# EST_MainV20_Output.net
KiCad netlist of a schematic drawn in Altium Designer
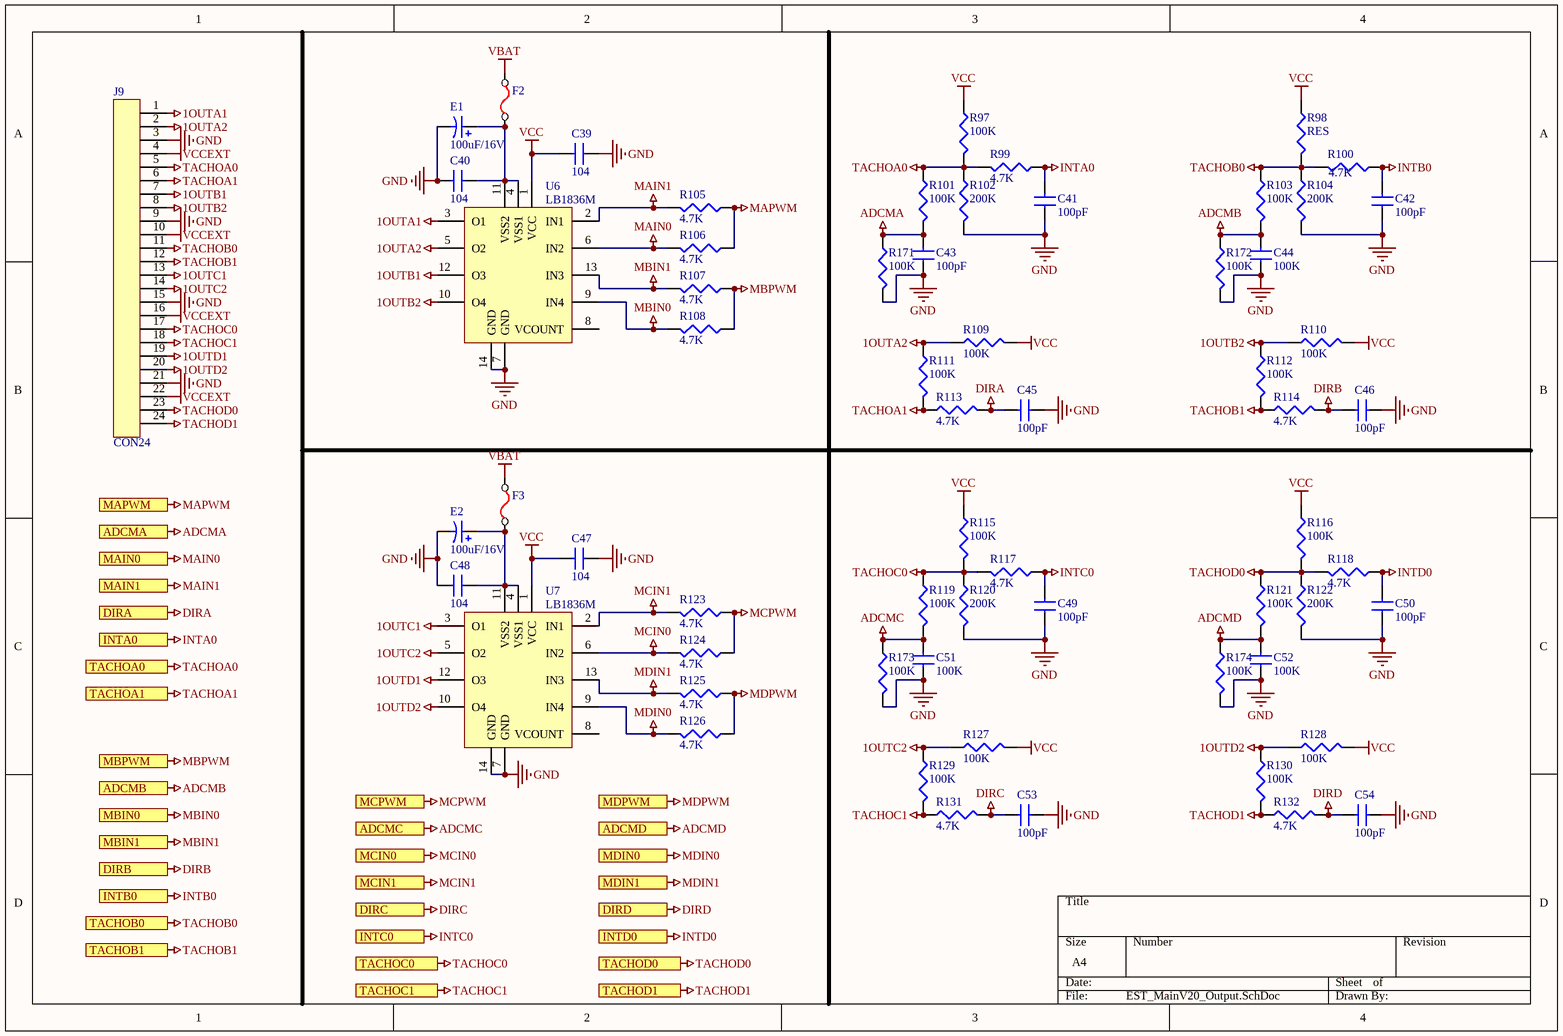
[diagram p0: EST_MainV20_Output.SchDoc]

(export (version "E")
  (design (tool "Eeschema 10.0.6"))
  (components
    (comp (ref "C39")
      (value "104")
      (footprint "CAP_0603")
      (description "Capacitor")
      (libsource (lib "模拟器件") (part "CAP"))
    )
    (comp (ref "C40")
      (value "104")
      (footprint "CAP_0603")
      (description "Capacitor")
      (libsource (lib "模拟器件") (part "CAP"))
    )
    (comp (ref "C41")
      (value "100pF")
      (footprint "CAP_0603")
      (description "Capacitor")
      (libsource (lib "模拟器件") (part "CAP"))
    )
    (comp (ref "C42")
      (value "100pF")
      (footprint "CAP_0603")
      (description "Capacitor")
      (libsource (lib "模拟器件") (part "CAP"))
    )
    (comp (ref "C43")
      (value "100pF")
      (footprint "CAP_0603")
      (description "Capacitor")
      (libsource (lib "模拟器件") (part "CAP"))
    )
    (comp (ref "C44")
      (value "100K")
      (footprint "CAP_0603")
      (description "Capacitor")
      (libsource (lib "模拟器件") (part "CAP"))
    )
    (comp (ref "C45")
      (value "100pF")
      (footprint "CAP_0603")
      (description "Capacitor")
      (libsource (lib "模拟器件") (part "CAP"))
    )
    (comp (ref "C46")
      (value "100pF")
      (footprint "CAP_0603")
      (description "Capacitor")
      (libsource (lib "模拟器件") (part "CAP"))
    )
    (comp (ref "C47")
      (value "104")
      (footprint "CAP_0603")
      (description "Capacitor")
      (libsource (lib "模拟器件") (part "CAP"))
    )
    (comp (ref "C48")
      (value "104")
      (footprint "CAP_0603")
      (description "Capacitor")
      (libsource (lib "模拟器件") (part "CAP"))
    )
    (comp (ref "C49")
      (value "100pF")
      (footprint "CAP_0603")
      (description "Capacitor")
      (libsource (lib "模拟器件") (part "CAP"))
    )
    (comp (ref "C50")
      (value "100pF")
      (footprint "CAP_0603")
      (description "Capacitor")
      (libsource (lib "模拟器件") (part "CAP"))
    )
    (comp (ref "C51")
      (value "100K")
      (footprint "CAP_0603")
      (description "Capacitor")
      (libsource (lib "模拟器件") (part "CAP"))
    )
    (comp (ref "C52")
      (value "100K")
      (footprint "CAP_0603")
      (description "Capacitor")
      (libsource (lib "模拟器件") (part "CAP"))
    )
    (comp (ref "C53")
      (value "100pF")
      (footprint "CAP_0603")
      (description "Capacitor")
      (libsource (lib "模拟器件") (part "CAP"))
    )
    (comp (ref "C54")
      (value "100pF")
      (footprint "CAP_0603")
      (description "Capacitor")
      (libsource (lib "模拟器件") (part "CAP"))
    )
    (comp (ref "E1")
      (value "100uF/16V")
      (footprint "1812")
      (description "Bi-Polar Capacitor")
      (libsource (lib "模拟器件") (part "CAP2"))
    )
    (comp (ref "E2")
      (value "100uF/16V")
      (footprint "1812")
      (description "Bi-Polar Capacitor")
      (libsource (lib "模拟器件") (part "CAP2"))
    )
    (comp (ref "F2")
      (value "FUSE")
      (footprint "1812")
      (description "Fuse")
      (libsource (lib "模拟器件") (part "FUSE"))
    )
    (comp (ref "F3")
      (value "FUSE")
      (footprint "1812")
      (description "Fuse")
      (libsource (lib "模拟器件") (part "FUSE"))
    )
    (comp (ref "J9") (value "CON24") (footprint "RJ11-4") (libsource (lib "模拟器件") (part "CON24")))
    (comp (ref "R97")
      (value "100K")
      (footprint "RES_0603")
      (description "Resistor")
      (libsource (lib "模拟器件") (part "RES"))
    )
    (comp (ref "R98")
      (value "RES")
      (footprint "RES_0603")
      (description "Resistor")
      (libsource (lib "模拟器件") (part "RES"))
    )
    (comp (ref "R99")
      (value "4.7K")
      (footprint "RES_0603")
      (description "Resistor")
      (libsource (lib "模拟器件") (part "RES"))
    )
    (comp (ref "R100")
      (value "4.7K")
      (footprint "RES_0603")
      (description "Resistor")
      (libsource (lib "模拟器件") (part "RES"))
    )
    (comp (ref "R101")
      (value "100K")
      (footprint "RES_0603")
      (description "Resistor")
      (libsource (lib "模拟器件") (part "RES"))
    )
    (comp (ref "R102")
      (value "200K")
      (footprint "RES_0603")
      (description "Resistor")
      (libsource (lib "模拟器件") (part "RES"))
    )
    (comp (ref "R103")
      (value "100K")
      (footprint "RES_0603")
      (description "Resistor")
      (libsource (lib "模拟器件") (part "RES"))
    )
    (comp (ref "R104")
      (value "200K")
      (footprint "RES_0603")
      (description "Resistor")
      (libsource (lib "模拟器件") (part "RES"))
    )
    (comp (ref "R105")
      (value "4.7K")
      (footprint "RES_0603")
      (description "Resistor")
      (libsource (lib "模拟器件") (part "RES"))
    )
    (comp (ref "R106")
      (value "4.7K")
      (footprint "RES_0603")
      (description "Resistor")
      (libsource (lib "模拟器件") (part "RES"))
    )
    (comp (ref "R107")
      (value "4.7K")
      (footprint "RES_0603")
      (description "Resistor")
      (libsource (lib "模拟器件") (part "RES"))
    )
    (comp (ref "R108")
      (value "4.7K")
      (footprint "RES_0603")
      (description "Resistor")
      (libsource (lib "模拟器件") (part "RES"))
    )
    (comp (ref "R109")
      (value "100K")
      (footprint "RES_0603")
      (description "Resistor")
      (libsource (lib "模拟器件") (part "RES"))
    )
    (comp (ref "R110")
      (value "100K")
      (footprint "RES_0603")
      (description "Resistor")
      (libsource (lib "模拟器件") (part "RES"))
    )
    (comp (ref "R111")
      (value "100K")
      (footprint "RES_0603")
      (description "Resistor")
      (libsource (lib "模拟器件") (part "RES"))
    )
    (comp (ref "R112")
      (value "100K")
      (footprint "RES_0603")
      (description "Resistor")
      (libsource (lib "模拟器件") (part "RES"))
    )
    (comp (ref "R113")
      (value "4.7K")
      (footprint "RES_0603")
      (description "Resistor")
      (libsource (lib "模拟器件") (part "RES"))
    )
    (comp (ref "R114")
      (value "4.7K")
      (footprint "RES_0603")
      (description "Resistor")
      (libsource (lib "模拟器件") (part "RES"))
    )
    (comp (ref "R115")
      (value "100K")
      (footprint "RES_0603")
      (description "Resistor")
      (libsource (lib "模拟器件") (part "RES"))
    )
    (comp (ref "R116")
      (value "100K")
      (footprint "RES_0603")
      (description "Resistor")
      (libsource (lib "模拟器件") (part "RES"))
    )
    (comp (ref "R117")
      (value "4.7K")
      (footprint "RES_0603")
      (description "Resistor")
      (libsource (lib "模拟器件") (part "RES"))
    )
    (comp (ref "R118")
      (value "4.7K")
      (footprint "RES_0603")
      (description "Resistor")
      (libsource (lib "模拟器件") (part "RES"))
    )
    (comp (ref "R119")
      (value "100K")
      (footprint "RES_0603")
      (description "Resistor")
      (libsource (lib "模拟器件") (part "RES"))
    )
    (comp (ref "R120")
      (value "200K")
      (footprint "RES_0603")
      (description "Resistor")
      (libsource (lib "模拟器件") (part "RES"))
    )
    (comp (ref "R121")
      (value "100K")
      (footprint "RES_0603")
      (description "Resistor")
      (libsource (lib "模拟器件") (part "RES"))
    )
    (comp (ref "R122")
      (value "200K")
      (footprint "RES_0603")
      (description "Resistor")
      (libsource (lib "模拟器件") (part "RES"))
    )
    (comp (ref "R123")
      (value "4.7K")
      (footprint "RES_0603")
      (description "Resistor")
      (libsource (lib "模拟器件") (part "RES"))
    )
    (comp (ref "R124")
      (value "4.7K")
      (footprint "RES_0603")
      (description "Resistor")
      (libsource (lib "模拟器件") (part "RES"))
    )
    (comp (ref "R125")
      (value "4.7K")
      (footprint "RES_0603")
      (description "Resistor")
      (libsource (lib "模拟器件") (part "RES"))
    )
    (comp (ref "R126")
      (value "4.7K")
      (footprint "RES_0603")
      (description "Resistor")
      (libsource (lib "模拟器件") (part "RES"))
    )
    (comp (ref "R127")
      (value "100K")
      (footprint "RES_0603")
      (description "Resistor")
      (libsource (lib "模拟器件") (part "RES"))
    )
    (comp (ref "R128")
      (value "100K")
      (footprint "RES_0603")
      (description "Resistor")
      (libsource (lib "模拟器件") (part "RES"))
    )
    (comp (ref "R129")
      (value "100K")
      (footprint "RES_0603")
      (description "Resistor")
      (libsource (lib "模拟器件") (part "RES"))
    )
    (comp (ref "R130")
      (value "100K")
      (footprint "RES_0603")
      (description "Resistor")
      (libsource (lib "模拟器件") (part "RES"))
    )
    (comp (ref "R131")
      (value "4.7K")
      (footprint "RES_0603")
      (description "Resistor")
      (libsource (lib "模拟器件") (part "RES"))
    )
    (comp (ref "R132")
      (value "4.7K")
      (footprint "RES_0603")
      (description "Resistor")
      (libsource (lib "模拟器件") (part "RES"))
    )
    (comp (ref "R171")
      (value "100K")
      (footprint "RES_0603")
      (description "Resistor")
      (libsource (lib "模拟器件") (part "RES"))
    )
    (comp (ref "R172")
      (value "100K")
      (footprint "RES_0603")
      (description "Resistor")
      (libsource (lib "模拟器件") (part "RES"))
    )
    (comp (ref "R173")
      (value "100K")
      (footprint "RES_0603")
      (description "Resistor")
      (libsource (lib "模拟器件") (part "RES"))
    )
    (comp (ref "R174")
      (value "100K")
      (footprint "RES_0603")
      (description "Resistor")
      (libsource (lib "模拟器件") (part "RES"))
    )
    (comp (ref "U6") (value "LB1836M") (footprint "LB1836") (libsource (lib "其它") (part "LM1836")))
    (comp (ref "U7") (value "LB1836M") (footprint "LB1836") (libsource (lib "其它") (part "LM1836")))
  )
  (nets
    (net (code "1") (name "1OUTA1") (class "Default")
      (node (ref "J9") (pin "1") (pinfunction "1_1") (pintype "passive"))
      (node (ref "U6") (pin "3") (pinfunction "O1_3") (pintype "passive"))
    )
    (net (code "2") (name "1OUTA2") (class "Default")
      (node (ref "J9") (pin "2") (pinfunction "2_2") (pintype "passive"))
      (node (ref "R109") (pin "2") (pinfunction "BOT_2") (pintype "passive"))
      (node (ref "R111") (pin "2") (pinfunction "BOT_2") (pintype "passive"))
      (node (ref "U6") (pin "5") (pinfunction "O2_5") (pintype "passive"))
    )
    (net (code "3") (name "1OUTB1") (class "Default")
      (node (ref "J9") (pin "7") (pinfunction "7_7") (pintype "passive"))
      (node (ref "U6") (pin "12") (pinfunction "O3_12") (pintype "passive"))
    )
    (net (code "4") (name "1OUTB2") (class "Default")
      (node (ref "J9") (pin "8") (pinfunction "8_8") (pintype "passive"))
      (node (ref "R110") (pin "2") (pinfunction "BOT_2") (pintype "passive"))
      (node (ref "R112") (pin "2") (pinfunction "BOT_2") (pintype "passive"))
      (node (ref "U6") (pin "10") (pinfunction "O4_10") (pintype "passive"))
    )
    (net (code "5") (name "1OUTC1") (class "Default")
      (node (ref "J9") (pin "13") (pinfunction "13_13") (pintype "passive"))
      (node (ref "U7") (pin "3") (pinfunction "O1_3") (pintype "passive"))
    )
    (net (code "6") (name "1OUTC2") (class "Default")
      (node (ref "J9") (pin "14") (pinfunction "14_14") (pintype "passive"))
      (node (ref "R127") (pin "2") (pinfunction "BOT_2") (pintype "passive"))
      (node (ref "R129") (pin "2") (pinfunction "BOT_2") (pintype "passive"))
      (node (ref "U7") (pin "5") (pinfunction "O2_5") (pintype "passive"))
    )
    (net (code "7") (name "1OUTD1") (class "Default")
      (node (ref "J9") (pin "19") (pinfunction "19_19") (pintype "passive"))
      (node (ref "U7") (pin "12") (pinfunction "O3_12") (pintype "passive"))
    )
    (net (code "8") (name "1OUTD2") (class "Default")
      (node (ref "J9") (pin "20") (pinfunction "20_20") (pintype "passive"))
      (node (ref "R128") (pin "2") (pinfunction "BOT_2") (pintype "passive"))
      (node (ref "R130") (pin "2") (pinfunction "BOT_2") (pintype "passive"))
      (node (ref "U7") (pin "10") (pinfunction "O4_10") (pintype "passive"))
    )
    (net (code "9") (name "ADCMA") (class "Default")
      (node (ref "C43") (pin "2") (pinfunction "2_2") (pintype "passive"))
      (node (ref "R101") (pin "1") (pinfunction "TOP_1") (pintype "passive"))
      (node (ref "R171") (pin "2") (pinfunction "BOT_2") (pintype "passive"))
    )
    (net (code "10") (name "ADCMB") (class "Default")
      (node (ref "C44") (pin "2") (pinfunction "2_2") (pintype "passive"))
      (node (ref "R103") (pin "1") (pinfunction "TOP_1") (pintype "passive"))
      (node (ref "R172") (pin "2") (pinfunction "BOT_2") (pintype "passive"))
    )
    (net (code "11") (name "ADCMC") (class "Default")
      (node (ref "C51") (pin "2") (pinfunction "2_2") (pintype "passive"))
      (node (ref "R119") (pin "1") (pinfunction "TOP_1") (pintype "passive"))
      (node (ref "R173") (pin "2") (pinfunction "BOT_2") (pintype "passive"))
    )
    (net (code "12") (name "ADCMD") (class "Default")
      (node (ref "C52") (pin "2") (pinfunction "2_2") (pintype "passive"))
      (node (ref "R121") (pin "1") (pinfunction "TOP_1") (pintype "passive"))
      (node (ref "R174") (pin "2") (pinfunction "BOT_2") (pintype "passive"))
    )
    (net (code "13") (name "DIRA") (class "Default")
      (node (ref "C45") (pin "2") (pinfunction "2_2") (pintype "passive"))
      (node (ref "R113") (pin "1") (pinfunction "TOP_1") (pintype "passive"))
    )
    (net (code "14") (name "DIRB") (class "Default")
      (node (ref "C46") (pin "2") (pinfunction "2_2") (pintype "passive"))
      (node (ref "R114") (pin "1") (pinfunction "TOP_1") (pintype "passive"))
    )
    (net (code "15") (name "DIRC") (class "Default")
      (node (ref "C53") (pin "2") (pinfunction "2_2") (pintype "passive"))
      (node (ref "R131") (pin "1") (pinfunction "TOP_1") (pintype "passive"))
    )
    (net (code "16") (name "DIRD") (class "Default")
      (node (ref "C54") (pin "2") (pinfunction "2_2") (pintype "passive"))
      (node (ref "R132") (pin "1") (pinfunction "TOP_1") (pintype "passive"))
    )
    (net (code "17") (name "GND") (class "Default")
      (node (ref "C39") (pin "2") (pinfunction "2_2") (pintype "passive"))
      (node (ref "C40") (pin "1") (pinfunction "1_1") (pintype "passive"))
      (node (ref "C41") (pin "1") (pinfunction "1_1") (pintype "passive"))
      (node (ref "C42") (pin "1") (pinfunction "1_1") (pintype "passive"))
      (node (ref "C43") (pin "1") (pinfunction "1_1") (pintype "passive"))
      (node (ref "C44") (pin "1") (pinfunction "1_1") (pintype "passive"))
      (node (ref "C45") (pin "1") (pinfunction "1_1") (pintype "passive"))
      (node (ref "C46") (pin "1") (pinfunction "1_1") (pintype "passive"))
      (node (ref "C47") (pin "2") (pinfunction "2_2") (pintype "passive"))
      (node (ref "C48") (pin "1") (pinfunction "1_1") (pintype "passive"))
      (node (ref "C49") (pin "1") (pinfunction "1_1") (pintype "passive"))
      (node (ref "C50") (pin "1") (pinfunction "1_1") (pintype "passive"))
      (node (ref "C51") (pin "1") (pinfunction "1_1") (pintype "passive"))
      (node (ref "C52") (pin "1") (pinfunction "1_1") (pintype "passive"))
      (node (ref "C53") (pin "1") (pinfunction "1_1") (pintype "passive"))
      (node (ref "C54") (pin "1") (pinfunction "1_1") (pintype "passive"))
      (node (ref "E1") (pin "2") (pinfunction "2_2") (pintype "passive"))
      (node (ref "E2") (pin "2") (pinfunction "2_2") (pintype "passive"))
      (node (ref "J9") (pin "15") (pinfunction "15_15") (pintype "passive"))
      (node (ref "J9") (pin "21") (pinfunction "21_21") (pintype "passive"))
      (node (ref "J9") (pin "3") (pinfunction "3_3") (pintype "passive"))
      (node (ref "J9") (pin "9") (pinfunction "9_9") (pintype "passive"))
      (node (ref "R102") (pin "1") (pinfunction "TOP_1") (pintype "passive"))
      (node (ref "R104") (pin "1") (pinfunction "TOP_1") (pintype "passive"))
      (node (ref "R120") (pin "1") (pinfunction "TOP_1") (pintype "passive"))
      (node (ref "R122") (pin "1") (pinfunction "TOP_1") (pintype "passive"))
      (node (ref "R171") (pin "1") (pinfunction "TOP_1") (pintype "passive"))
      (node (ref "R172") (pin "1") (pinfunction "TOP_1") (pintype "passive"))
      (node (ref "R173") (pin "1") (pinfunction "TOP_1") (pintype "passive"))
      (node (ref "R174") (pin "1") (pinfunction "TOP_1") (pintype "passive"))
      (node (ref "U6") (pin "14") (pinfunction "GND_14") (pintype "passive"))
      (node (ref "U6") (pin "7") (pinfunction "GND_7") (pintype "passive"))
      (node (ref "U7") (pin "14") (pinfunction "GND_14") (pintype "passive"))
      (node (ref "U7") (pin "7") (pinfunction "GND_7") (pintype "passive"))
    )
    (net (code "18") (name "INTA0") (class "Default")
      (node (ref "C41") (pin "2") (pinfunction "2_2") (pintype "passive"))
      (node (ref "R99") (pin "2") (pinfunction "BOT_2") (pintype "passive"))
    )
    (net (code "19") (name "INTB0") (class "Default")
      (node (ref "C42") (pin "2") (pinfunction "2_2") (pintype "passive"))
      (node (ref "R100") (pin "2") (pinfunction "BOT_2") (pintype "passive"))
    )
    (net (code "20") (name "INTC0") (class "Default")
      (node (ref "C49") (pin "2") (pinfunction "2_2") (pintype "passive"))
      (node (ref "R117") (pin "2") (pinfunction "BOT_2") (pintype "passive"))
    )
    (net (code "21") (name "INTD0") (class "Default")
      (node (ref "C50") (pin "2") (pinfunction "2_2") (pintype "passive"))
      (node (ref "R118") (pin "2") (pinfunction "BOT_2") (pintype "passive"))
    )
    (net (code "22") (name "MAIN0") (class "Default")
      (node (ref "R106") (pin "1") (pinfunction "TOP_1") (pintype "passive"))
      (node (ref "U6") (pin "6") (pinfunction "IN2_6") (pintype "passive"))
    )
    (net (code "23") (name "MAIN1") (class "Default")
      (node (ref "R105") (pin "1") (pinfunction "TOP_1") (pintype "passive"))
      (node (ref "U6") (pin "2") (pinfunction "IN1_2") (pintype "passive"))
    )
    (net (code "24") (name "MAPWM") (class "Default")
      (node (ref "R105") (pin "2") (pinfunction "BOT_2") (pintype "passive"))
      (node (ref "R106") (pin "2") (pinfunction "BOT_2") (pintype "passive"))
    )
    (net (code "25") (name "MBIN0") (class "Default")
      (node (ref "R108") (pin "1") (pinfunction "TOP_1") (pintype "passive"))
      (node (ref "U6") (pin "9") (pinfunction "IN4_9") (pintype "passive"))
    )
    (net (code "26") (name "MBIN1") (class "Default")
      (node (ref "R107") (pin "1") (pinfunction "TOP_1") (pintype "passive"))
      (node (ref "U6") (pin "13") (pinfunction "IN3_13") (pintype "passive"))
    )
    (net (code "27") (name "MBPWM") (class "Default")
      (node (ref "R107") (pin "2") (pinfunction "BOT_2") (pintype "passive"))
      (node (ref "R108") (pin "2") (pinfunction "BOT_2") (pintype "passive"))
    )
    (net (code "28") (name "MCIN0") (class "Default")
      (node (ref "R124") (pin "1") (pinfunction "TOP_1") (pintype "passive"))
      (node (ref "U7") (pin "6") (pinfunction "IN2_6") (pintype "passive"))
    )
    (net (code "29") (name "MCIN1") (class "Default")
      (node (ref "R123") (pin "1") (pinfunction "TOP_1") (pintype "passive"))
      (node (ref "U7") (pin "2") (pinfunction "IN1_2") (pintype "passive"))
    )
    (net (code "30") (name "MCPWM") (class "Default")
      (node (ref "R123") (pin "2") (pinfunction "BOT_2") (pintype "passive"))
      (node (ref "R124") (pin "2") (pinfunction "BOT_2") (pintype "passive"))
    )
    (net (code "31") (name "MDIN0") (class "Default")
      (node (ref "R126") (pin "1") (pinfunction "TOP_1") (pintype "passive"))
      (node (ref "U7") (pin "9") (pinfunction "IN4_9") (pintype "passive"))
    )
    (net (code "32") (name "MDIN1") (class "Default")
      (node (ref "R125") (pin "1") (pinfunction "TOP_1") (pintype "passive"))
      (node (ref "U7") (pin "13") (pinfunction "IN3_13") (pintype "passive"))
    )
    (net (code "33") (name "MDPWM") (class "Default")
      (node (ref "R125") (pin "2") (pinfunction "BOT_2") (pintype "passive"))
      (node (ref "R126") (pin "2") (pinfunction "BOT_2") (pintype "passive"))
    )
    (net (code "34") (name "Net-(U6-VSS1)") (class "Default")
      (node (ref "C40") (pin "2") (pinfunction "2_2") (pintype "passive"))
      (node (ref "E1") (pin "1") (pinfunction "1_1") (pintype "passive"))
      (node (ref "F2") (pin "2") (pinfunction "2_2") (pintype "passive"))
      (node (ref "U6") (pin "11") (pinfunction "VSS2_11") (pintype "passive"))
      (node (ref "U6") (pin "4") (pinfunction "VSS1_4") (pintype "passive"))
    )
    (net (code "35") (name "Net-(U7-VSS1)") (class "Default")
      (node (ref "C48") (pin "2") (pinfunction "2_2") (pintype "passive"))
      (node (ref "E2") (pin "1") (pinfunction "1_1") (pintype "passive"))
      (node (ref "F3") (pin "2") (pinfunction "2_2") (pintype "passive"))
      (node (ref "U7") (pin "11") (pinfunction "VSS2_11") (pintype "passive"))
      (node (ref "U7") (pin "4") (pinfunction "VSS1_4") (pintype "passive"))
    )
    (net (code "36") (name "TACHOA0") (class "Default")
      (node (ref "J9") (pin "5") (pinfunction "5_5") (pintype "passive"))
      (node (ref "R101") (pin "2") (pinfunction "BOT_2") (pintype "passive"))
      (node (ref "R102") (pin "2") (pinfunction "BOT_2") (pintype "passive"))
      (node (ref "R97") (pin "1") (pinfunction "TOP_1") (pintype "passive"))
      (node (ref "R99") (pin "1") (pinfunction "TOP_1") (pintype "passive"))
    )
    (net (code "37") (name "TACHOA1") (class "Default")
      (node (ref "J9") (pin "6") (pinfunction "6_6") (pintype "passive"))
      (node (ref "R111") (pin "1") (pinfunction "TOP_1") (pintype "passive"))
      (node (ref "R113") (pin "2") (pinfunction "BOT_2") (pintype "passive"))
    )
    (net (code "38") (name "TACHOB0") (class "Default")
      (node (ref "J9") (pin "11") (pinfunction "11_11") (pintype "passive"))
      (node (ref "R100") (pin "1") (pinfunction "TOP_1") (pintype "passive"))
      (node (ref "R103") (pin "2") (pinfunction "BOT_2") (pintype "passive"))
      (node (ref "R104") (pin "2") (pinfunction "BOT_2") (pintype "passive"))
      (node (ref "R98") (pin "1") (pinfunction "TOP_1") (pintype "passive"))
    )
    (net (code "39") (name "TACHOB1") (class "Default")
      (node (ref "J9") (pin "12") (pinfunction "12_12") (pintype "passive"))
      (node (ref "R112") (pin "1") (pinfunction "TOP_1") (pintype "passive"))
      (node (ref "R114") (pin "2") (pinfunction "BOT_2") (pintype "passive"))
    )
    (net (code "40") (name "TACHOC0") (class "Default")
      (node (ref "J9") (pin "17") (pinfunction "17_17") (pintype "passive"))
      (node (ref "R115") (pin "1") (pinfunction "TOP_1") (pintype "passive"))
      (node (ref "R117") (pin "1") (pinfunction "TOP_1") (pintype "passive"))
      (node (ref "R119") (pin "2") (pinfunction "BOT_2") (pintype "passive"))
      (node (ref "R120") (pin "2") (pinfunction "BOT_2") (pintype "passive"))
    )
    (net (code "41") (name "TACHOC1") (class "Default")
      (node (ref "J9") (pin "18") (pinfunction "18_18") (pintype "passive"))
      (node (ref "R129") (pin "1") (pinfunction "TOP_1") (pintype "passive"))
      (node (ref "R131") (pin "2") (pinfunction "BOT_2") (pintype "passive"))
    )
    (net (code "42") (name "TACHOD0") (class "Default")
      (node (ref "J9") (pin "23") (pinfunction "23_23") (pintype "passive"))
      (node (ref "R116") (pin "1") (pinfunction "TOP_1") (pintype "passive"))
      (node (ref "R118") (pin "1") (pinfunction "TOP_1") (pintype "passive"))
      (node (ref "R121") (pin "2") (pinfunction "BOT_2") (pintype "passive"))
      (node (ref "R122") (pin "2") (pinfunction "BOT_2") (pintype "passive"))
    )
    (net (code "43") (name "TACHOD1") (class "Default")
      (node (ref "J9") (pin "24") (pinfunction "24_24") (pintype "passive"))
      (node (ref "R130") (pin "1") (pinfunction "TOP_1") (pintype "passive"))
      (node (ref "R132") (pin "2") (pinfunction "BOT_2") (pintype "passive"))
    )
    (net (code "44") (name "VBAT") (class "Default")
      (node (ref "F2") (pin "1") (pinfunction "1_1") (pintype "passive"))
      (node (ref "F3") (pin "1") (pinfunction "1_1") (pintype "passive"))
    )
    (net (code "45") (name "VCC") (class "Default")
      (node (ref "C39") (pin "1") (pinfunction "1_1") (pintype "passive"))
      (node (ref "C47") (pin "1") (pinfunction "1_1") (pintype "passive"))
      (node (ref "R109") (pin "1") (pinfunction "TOP_1") (pintype "passive"))
      (node (ref "R110") (pin "1") (pinfunction "TOP_1") (pintype "passive"))
      (node (ref "R115") (pin "2") (pinfunction "BOT_2") (pintype "passive"))
      (node (ref "R116") (pin "2") (pinfunction "BOT_2") (pintype "passive"))
      (node (ref "R127") (pin "1") (pinfunction "TOP_1") (pintype "passive"))
      (node (ref "R128") (pin "1") (pinfunction "TOP_1") (pintype "passive"))
      (node (ref "R97") (pin "2") (pinfunction "BOT_2") (pintype "passive"))
      (node (ref "R98") (pin "2") (pinfunction "BOT_2") (pintype "passive"))
      (node (ref "U6") (pin "1") (pinfunction "VCC_1") (pintype "passive"))
      (node (ref "U7") (pin "1") (pinfunction "VCC_1") (pintype "passive"))
    )
    (net (code "46") (name "VCCEXT") (class "Default")
      (node (ref "J9") (pin "10") (pinfunction "10_10") (pintype "passive"))
      (node (ref "J9") (pin "16") (pinfunction "16_16") (pintype "passive"))
      (node (ref "J9") (pin "22") (pinfunction "22_22") (pintype "passive"))
      (node (ref "J9") (pin "4") (pinfunction "4_4") (pintype "passive"))
    )
    (net (code "47") (name "unconnected-(U6-VCOUNT-Pad8)") (class "Default")
      (node (ref "U6") (pin "8") (pinfunction "VCOUNT_8") (pintype "passive"))
    )
    (net (code "48") (name "unconnected-(U7-VCOUNT-Pad8)") (class "Default")
      (node (ref "U7") (pin "8") (pinfunction "VCOUNT_8") (pintype "passive"))
    )
  )
)
